# 12_LMS2_Power.net
KiCad netlist of a schematic drawn in Altium Designer
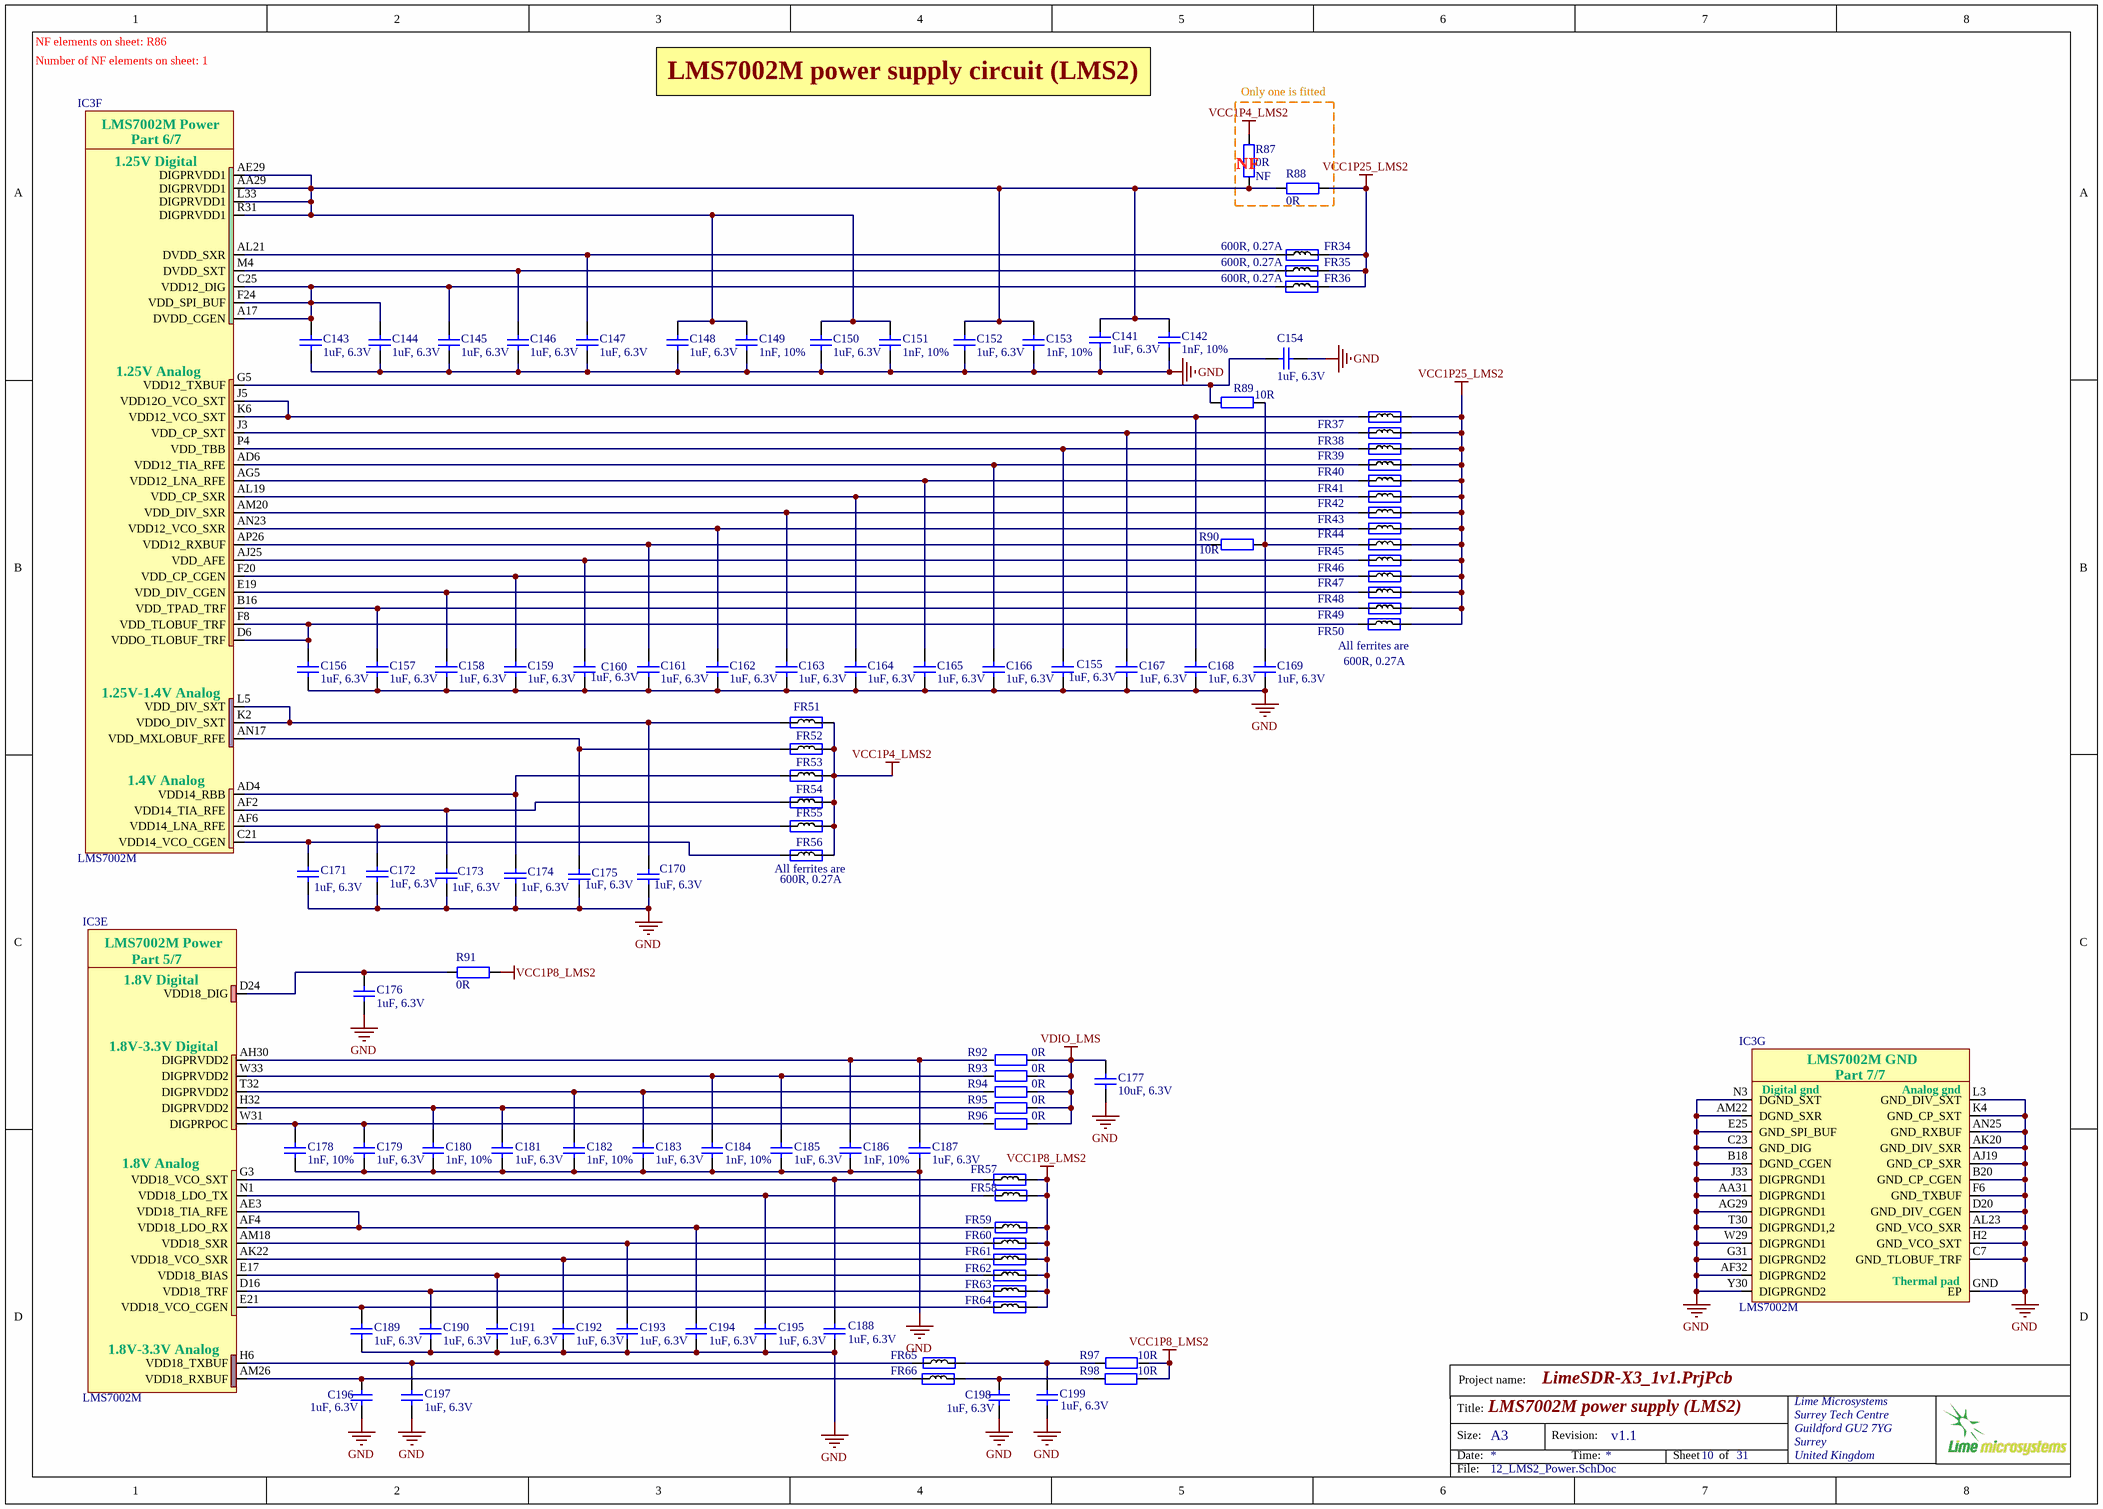
[diagram p0: 12_LMS2_Power.SchDoc]

(export (version "E")
  (design (tool "Eeschema 10.0.6"))
  (components
    (comp (ref "C141")
      (value "1uF, 6.3V")
      (footprint "CAP0201")
      (fields (field (name "TOLERANCE") "±20%") (field (name "MANUFACTURER") "TDK Corporation"))
      (libsource (lib "") (part "Cap_0402_1"))
    )
    (comp (ref "C142")
      (value "1nF, 10%")
      (footprint "CAP0201")
      (fields (field (name "TOLERANCE") "±10%") (field (name "MANUFACTURER") "TDK Corporation"))
      (libsource (lib "") (part "Cap_0402_1"))
    )
    (comp (ref "C143")
      (value "1uF, 6.3V")
      (footprint "CAP0201")
      (fields (field (name "TOLERANCE") "±20%") (field (name "MANUFACTURER") "TDK Corporation"))
      (libsource (lib "") (part "Cap_0402_2"))
    )
    (comp (ref "C144")
      (value "1uF, 6.3V")
      (footprint "CAP0201")
      (fields (field (name "TOLERANCE") "±20%") (field (name "MANUFACTURER") "TDK Corporation"))
      (libsource (lib "") (part "Cap_0402_2"))
    )
    (comp (ref "C145")
      (value "1uF, 6.3V")
      (footprint "CAP0201")
      (fields (field (name "TOLERANCE") "±20%") (field (name "MANUFACTURER") "TDK Corporation"))
      (libsource (lib "") (part "Cap_0402_2"))
    )
    (comp (ref "C146")
      (value "1uF, 6.3V")
      (footprint "CAP0201")
      (fields (field (name "TOLERANCE") "±20%") (field (name "MANUFACTURER") "TDK Corporation"))
      (libsource (lib "") (part "Cap_0402_1"))
    )
    (comp (ref "C147")
      (value "1uF, 6.3V")
      (footprint "CAP0201")
      (fields (field (name "TOLERANCE") "±20%") (field (name "MANUFACTURER") "TDK Corporation"))
      (libsource (lib "") (part "Cap_0402_2"))
    )
    (comp (ref "C148")
      (value "1uF, 6.3V")
      (footprint "CAP0201")
      (fields (field (name "TOLERANCE") "±20%") (field (name "MANUFACTURER") "TDK Corporation"))
      (libsource (lib "") (part "Cap_0402_1"))
    )
    (comp (ref "C149")
      (value "1nF, 10%")
      (footprint "CAP0201")
      (fields (field (name "TOLERANCE") "±10%") (field (name "MANUFACTURER") "TDK Corporation"))
      (libsource (lib "") (part "Cap_0402_1"))
    )
    (comp (ref "C150")
      (value "1uF, 6.3V")
      (footprint "CAP0201")
      (fields (field (name "TOLERANCE") "±20%") (field (name "MANUFACTURER") "TDK Corporation"))
      (libsource (lib "") (part "Cap_0402_1"))
    )
    (comp (ref "C151")
      (value "1nF, 10%")
      (footprint "CAP0201")
      (fields (field (name "TOLERANCE") "±10%") (field (name "MANUFACTURER") "TDK Corporation"))
      (libsource (lib "") (part "Cap_0402_1"))
    )
    (comp (ref "C152")
      (value "1uF, 6.3V")
      (footprint "CAP0201")
      (fields (field (name "TOLERANCE") "±20%") (field (name "MANUFACTURER") "TDK Corporation"))
      (libsource (lib "") (part "Cap_0402_1"))
    )
    (comp (ref "C153")
      (value "1nF, 10%")
      (footprint "CAP0201")
      (fields (field (name "TOLERANCE") "±10%") (field (name "MANUFACTURER") "TDK Corporation"))
      (libsource (lib "") (part "Cap_0402_1"))
    )
    (comp (ref "C154")
      (value "1uF, 6.3V")
      (footprint "CAP0201")
      (fields (field (name "TOLERANCE") "±20%") (field (name "MANUFACTURER") "TDK Corporation"))
      (libsource (lib "") (part "Cap_0402_4"))
    )
    (comp (ref "C155")
      (value "1uF, 6.3V")
      (footprint "CAP0201")
      (fields (field (name "TOLERANCE") "±20%") (field (name "MANUFACTURER") "TDK Corporation"))
      (libsource (lib "") (part "Cap_0402_2"))
    )
    (comp (ref "C156")
      (value "1uF, 6.3V")
      (footprint "CAP0201")
      (fields (field (name "TOLERANCE") "±20%") (field (name "MANUFACTURER") "TDK Corporation"))
      (libsource (lib "") (part "Cap_0402_2"))
    )
    (comp (ref "C157")
      (value "1uF, 6.3V")
      (footprint "CAP0201")
      (fields (field (name "TOLERANCE") "±20%") (field (name "MANUFACTURER") "TDK Corporation"))
      (libsource (lib "") (part "Cap_0402_2"))
    )
    (comp (ref "C158")
      (value "1uF, 6.3V")
      (footprint "CAP0201")
      (fields (field (name "TOLERANCE") "±20%") (field (name "MANUFACTURER") "TDK Corporation"))
      (libsource (lib "") (part "Cap_0402_2"))
    )
    (comp (ref "C159")
      (value "1uF, 6.3V")
      (footprint "CAP0201")
      (fields (field (name "TOLERANCE") "±20%") (field (name "MANUFACTURER") "TDK Corporation"))
      (libsource (lib "") (part "Cap_0402_1"))
    )
    (comp (ref "C160")
      (value "1uF, 6.3V")
      (footprint "CAP0201")
      (fields (field (name "TOLERANCE") "±20%") (field (name "MANUFACTURER") "TDK Corporation"))
      (libsource (lib "") (part "Cap_0402_2"))
    )
    (comp (ref "C161")
      (value "1uF, 6.3V")
      (footprint "CAP0201")
      (fields (field (name "TOLERANCE") "±20%") (field (name "MANUFACTURER") "TDK Corporation"))
      (libsource (lib "") (part "Cap_0402_2"))
    )
    (comp (ref "C162")
      (value "1uF, 6.3V")
      (footprint "CAP0201")
      (fields (field (name "TOLERANCE") "±20%") (field (name "MANUFACTURER") "TDK Corporation"))
      (libsource (lib "") (part "Cap_0402_2"))
    )
    (comp (ref "C163")
      (value "1uF, 6.3V")
      (footprint "CAP0201")
      (fields (field (name "TOLERANCE") "±20%") (field (name "MANUFACTURER") "TDK Corporation"))
      (libsource (lib "") (part "Cap_0402_2"))
    )
    (comp (ref "C164")
      (value "1uF, 6.3V")
      (footprint "CAP0201")
      (fields (field (name "TOLERANCE") "±20%") (field (name "MANUFACTURER") "TDK Corporation"))
      (libsource (lib "") (part "Cap_0402_2"))
    )
    (comp (ref "C165")
      (value "1uF, 6.3V")
      (footprint "CAP0201")
      (fields (field (name "TOLERANCE") "±20%") (field (name "MANUFACTURER") "TDK Corporation"))
      (libsource (lib "") (part "Cap_0402_2"))
    )
    (comp (ref "C166")
      (value "1uF, 6.3V")
      (footprint "CAP0201")
      (fields (field (name "TOLERANCE") "±20%") (field (name "MANUFACTURER") "TDK Corporation"))
      (libsource (lib "") (part "Cap_0402_1"))
    )
    (comp (ref "C167")
      (value "1uF, 6.3V")
      (footprint "CAP0201")
      (fields (field (name "TOLERANCE") "±20%") (field (name "MANUFACTURER") "TDK Corporation"))
      (libsource (lib "") (part "Cap_0402_2"))
    )
    (comp (ref "C168")
      (value "1uF, 6.3V")
      (footprint "CAP0201")
      (fields (field (name "TOLERANCE") "±20%") (field (name "MANUFACTURER") "TDK Corporation"))
      (libsource (lib "") (part "Cap_0402_1"))
    )
    (comp (ref "C169")
      (value "1uF, 6.3V")
      (footprint "CAP0201")
      (fields (field (name "TOLERANCE") "±20%") (field (name "MANUFACTURER") "TDK Corporation"))
      (libsource (lib "") (part "Cap_0402_1"))
    )
    (comp (ref "C170")
      (value "1uF, 6.3V")
      (footprint "CAP0201")
      (fields (field (name "TOLERANCE") "±20%") (field (name "MANUFACTURER") "TDK Corporation"))
      (libsource (lib "") (part "Cap_0402_2"))
    )
    (comp (ref "C171")
      (value "1uF, 6.3V")
      (footprint "CAP0201")
      (fields (field (name "TOLERANCE") "±20%") (field (name "MANUFACTURER") "TDK Corporation"))
      (libsource (lib "") (part "Cap_0402_2"))
    )
    (comp (ref "C172")
      (value "1uF, 6.3V")
      (footprint "CAP0201")
      (fields (field (name "TOLERANCE") "±20%") (field (name "MANUFACTURER") "TDK Corporation"))
      (libsource (lib "") (part "Cap_0402_2"))
    )
    (comp (ref "C173")
      (value "1uF, 6.3V")
      (footprint "CAP0201")
      (fields (field (name "TOLERANCE") "±20%") (field (name "MANUFACTURER") "TDK Corporation"))
      (libsource (lib "") (part "Cap_0402_3"))
    )
    (comp (ref "C174")
      (value "1uF, 6.3V")
      (footprint "CAP0201")
      (fields (field (name "TOLERANCE") "±20%") (field (name "MANUFACTURER") "TDK Corporation"))
      (libsource (lib "") (part "Cap_0402_3"))
    )
    (comp (ref "C175")
      (value "1uF, 6.3V")
      (footprint "CAP0201")
      (fields (field (name "TOLERANCE") "±20%") (field (name "MANUFACTURER") "TDK Corporation"))
      (libsource (lib "") (part "Cap_0402_2"))
    )
    (comp (ref "C176")
      (value "1uF, 6.3V")
      (footprint "CAP0201")
      (fields (field (name "TOLERANCE") "±20%") (field (name "MANUFACTURER") "TDK Corporation"))
      (libsource (lib "LimeMicroAltiumLib_schLib") (part "Cap_0402"))
    )
    (comp (ref "C177")
      (value "10uF, 6.3V")
      (footprint "CAP0603")
      (fields (field (name "TOLERANCE") "±20%") (field (name "MANUFACTURER") "Yageo"))
      (libsource (lib "LimeFPGAboard_schLib") (part "Cap_0603"))
    )
    (comp (ref "C178")
      (value "1nF, 10%")
      (footprint "CAP0201")
      (fields (field (name "TOLERANCE") "±10%") (field (name "MANUFACTURER") "TDK Corporation"))
      (libsource (lib "LimeMicroAltiumLib_schLib") (part "Cap_0402"))
    )
    (comp (ref "C179")
      (value "1uF, 6.3V")
      (footprint "CAP0201")
      (fields (field (name "TOLERANCE") "±20%") (field (name "MANUFACTURER") "TDK Corporation"))
      (libsource (lib "LimeMicroAltiumLib_schLib") (part "Cap_0402"))
    )
    (comp (ref "C180")
      (value "1nF, 10%")
      (footprint "CAP0201")
      (fields (field (name "TOLERANCE") "±10%") (field (name "MANUFACTURER") "TDK Corporation"))
      (libsource (lib "LimeMicroAltiumLib_schLib") (part "Cap_0402"))
    )
    (comp (ref "C181")
      (value "1uF, 6.3V")
      (footprint "CAP0201")
      (fields (field (name "TOLERANCE") "±20%") (field (name "MANUFACTURER") "TDK Corporation"))
      (libsource (lib "LimeMicroAltiumLib_schLib") (part "Cap_0402"))
    )
    (comp (ref "C182")
      (value "1nF, 10%")
      (footprint "CAP0201")
      (fields (field (name "TOLERANCE") "±10%") (field (name "MANUFACTURER") "TDK Corporation"))
      (libsource (lib "LimeMicroAltiumLib_schLib") (part "Cap_0402"))
    )
    (comp (ref "C183")
      (value "1uF, 6.3V")
      (footprint "CAP0201")
      (fields (field (name "TOLERANCE") "±20%") (field (name "MANUFACTURER") "TDK Corporation"))
      (libsource (lib "LimeMicroAltiumLib_schLib") (part "Cap_0402"))
    )
    (comp (ref "C184")
      (value "1nF, 10%")
      (footprint "CAP0201")
      (fields (field (name "TOLERANCE") "±10%") (field (name "MANUFACTURER") "TDK Corporation"))
      (libsource (lib "LimeMicroAltiumLib_schLib") (part "Cap_0402"))
    )
    (comp (ref "C185")
      (value "1uF, 6.3V")
      (footprint "CAP0201")
      (fields (field (name "TOLERANCE") "±20%") (field (name "MANUFACTURER") "TDK Corporation"))
      (libsource (lib "LimeMicroAltiumLib_schLib") (part "Cap_0402"))
    )
    (comp (ref "C186")
      (value "1nF, 10%")
      (footprint "CAP0201")
      (fields (field (name "TOLERANCE") "±10%") (field (name "MANUFACTURER") "TDK Corporation"))
      (libsource (lib "LimeMicroAltiumLib_schLib") (part "Cap_0402"))
    )
    (comp (ref "C187")
      (value "1uF, 6.3V")
      (footprint "CAP0201")
      (fields (field (name "TOLERANCE") "±20%") (field (name "MANUFACTURER") "TDK Corporation"))
      (libsource (lib "LimeMicroAltiumLib_schLib") (part "Cap_0402"))
    )
    (comp (ref "C188")
      (value "1uF, 6.3V")
      (footprint "CAP0201")
      (fields (field (name "TOLERANCE") "±20%") (field (name "MANUFACTURER") "TDK Corporation"))
      (libsource (lib "LimeMicroAltiumLib_schLib") (part "Cap_0402"))
    )
    (comp (ref "C189")
      (value "1uF, 6.3V")
      (footprint "CAP0201")
      (fields (field (name "TOLERANCE") "±20%") (field (name "MANUFACTURER") "TDK Corporation"))
      (libsource (lib "LimeMicroAltiumLib_schLib") (part "Cap_0402"))
    )
    (comp (ref "C190")
      (value "1uF, 6.3V")
      (footprint "CAP0201")
      (fields (field (name "TOLERANCE") "±20%") (field (name "MANUFACTURER") "TDK Corporation"))
      (libsource (lib "LimeMicroAltiumLib_schLib") (part "Cap_0402"))
    )
    (comp (ref "C191")
      (value "1uF, 6.3V")
      (footprint "CAP0201")
      (fields (field (name "TOLERANCE") "±20%") (field (name "MANUFACTURER") "TDK Corporation"))
      (libsource (lib "LimeMicroAltiumLib_schLib") (part "Cap_0402"))
    )
    (comp (ref "C192")
      (value "1uF, 6.3V")
      (footprint "CAP0201")
      (fields (field (name "TOLERANCE") "±20%") (field (name "MANUFACTURER") "TDK Corporation"))
      (libsource (lib "LimeMicroAltiumLib_schLib") (part "Cap_0402"))
    )
    (comp (ref "C193")
      (value "1uF, 6.3V")
      (footprint "CAP0201")
      (fields (field (name "TOLERANCE") "±20%") (field (name "MANUFACTURER") "TDK Corporation"))
      (libsource (lib "LimeMicroAltiumLib_schLib") (part "Cap_0402"))
    )
    (comp (ref "C194")
      (value "1uF, 6.3V")
      (footprint "CAP0201")
      (fields (field (name "TOLERANCE") "±20%") (field (name "MANUFACTURER") "TDK Corporation"))
      (libsource (lib "LimeMicroAltiumLib_schLib") (part "Cap_0402"))
    )
    (comp (ref "C195")
      (value "1uF, 6.3V")
      (footprint "CAP0201")
      (fields (field (name "TOLERANCE") "±20%") (field (name "MANUFACTURER") "TDK Corporation"))
      (libsource (lib "LimeMicroAltiumLib_schLib") (part "Cap_0402"))
    )
    (comp (ref "C196")
      (value "1uF, 6.3V")
      (footprint "CAP0201")
      (fields (field (name "TOLERANCE") "±20%") (field (name "MANUFACTURER") "TDK Corporation"))
      (libsource (lib "LimeMicroAltiumLib_schLib") (part "Cap_0402"))
    )
    (comp (ref "C197")
      (value "1uF, 6.3V")
      (footprint "CAP0201")
      (fields (field (name "TOLERANCE") "±20%") (field (name "MANUFACTURER") "TDK Corporation"))
      (libsource (lib "LimeMicroAltiumLib_schLib") (part "Cap_0402"))
    )
    (comp (ref "C198")
      (value "1uF, 6.3V")
      (footprint "CAP0201")
      (fields (field (name "TOLERANCE") "±20%") (field (name "MANUFACTURER") "TDK Corporation"))
      (libsource (lib "LimeMicroAltiumLib_schLib") (part "Cap_0402"))
    )
    (comp (ref "C199")
      (value "1uF, 6.3V")
      (footprint "CAP0201")
      (fields (field (name "TOLERANCE") "±20%") (field (name "MANUFACTURER") "TDK Corporation"))
      (libsource (lib "LimeMicroAltiumLib_schLib") (part "Cap_0402"))
    )
    (comp (ref "FR34")
      (value "600R, 0.27A")
      (footprint "RES0201")
      (fields (field (name "MANUFACTURER") "Taiyo Yuden"))
      (libsource (lib "") (part "Ferrite_1"))
    )
    (comp (ref "FR35")
      (value "600R, 0.27A")
      (footprint "RES0201")
      (fields (field (name "MANUFACTURER") "Taiyo Yuden"))
      (libsource (lib "LimeMicroAltiumLib_schLib") (part "Ferrite"))
    )
    (comp (ref "FR36")
      (value "600R, 0.27A")
      (footprint "RES0201")
      (fields (field (name "MANUFACTURER") "Taiyo Yuden"))
      (libsource (lib "LimeMicroAltiumLib_schLib") (part "Ferrite"))
    )
    (comp (ref "FR37")
      (value "600R, 0.27A")
      (footprint "RES0201")
      (fields (field (name "MANUFACTURER") "Taiyo Yuden"))
      (libsource (lib "") (part "Ferrite_1"))
    )
    (comp (ref "FR38")
      (value "600R, 0.27A")
      (footprint "RES0201")
      (fields (field (name "MANUFACTURER") "Taiyo Yuden"))
      (libsource (lib "") (part "Ferrite_1"))
    )
    (comp (ref "FR39")
      (value "600R, 0.27A")
      (footprint "RES0201")
      (fields (field (name "MANUFACTURER") "Taiyo Yuden"))
      (libsource (lib "") (part "Ferrite_1"))
    )
    (comp (ref "FR40")
      (value "600R, 0.27A")
      (footprint "RES0201")
      (fields (field (name "MANUFACTURER") "Taiyo Yuden"))
      (libsource (lib "") (part "Ferrite_1"))
    )
    (comp (ref "FR41")
      (value "600R, 0.27A")
      (footprint "RES0201")
      (fields (field (name "MANUFACTURER") "Taiyo Yuden"))
      (libsource (lib "") (part "Ferrite_1"))
    )
    (comp (ref "FR42")
      (value "600R, 0.27A")
      (footprint "RES0201")
      (fields (field (name "MANUFACTURER") "Taiyo Yuden"))
      (libsource (lib "") (part "Ferrite_1"))
    )
    (comp (ref "FR43")
      (value "600R, 0.27A")
      (footprint "RES0201")
      (fields (field (name "MANUFACTURER") "Taiyo Yuden"))
      (libsource (lib "") (part "Ferrite_1"))
    )
    (comp (ref "FR44")
      (value "600R, 0.27A")
      (footprint "RES0201")
      (fields (field (name "MANUFACTURER") "Taiyo Yuden"))
      (libsource (lib "") (part "Ferrite_1"))
    )
    (comp (ref "FR45")
      (value "600R, 0.27A")
      (footprint "RES0201")
      (fields (field (name "MANUFACTURER") "Taiyo Yuden"))
      (libsource (lib "") (part "Ferrite_1"))
    )
    (comp (ref "FR46")
      (value "600R, 0.27A")
      (footprint "RES0201")
      (fields (field (name "MANUFACTURER") "Taiyo Yuden"))
      (libsource (lib "") (part "Ferrite_1"))
    )
    (comp (ref "FR47")
      (value "600R, 0.27A")
      (footprint "RES0201")
      (fields (field (name "MANUFACTURER") "Taiyo Yuden"))
      (libsource (lib "") (part "Ferrite_1"))
    )
    (comp (ref "FR48")
      (value "600R, 0.27A")
      (footprint "RES0201")
      (fields (field (name "MANUFACTURER") "Taiyo Yuden"))
      (libsource (lib "") (part "Ferrite_1"))
    )
    (comp (ref "FR49")
      (value "600R, 0.27A")
      (footprint "RES0201")
      (fields (field (name "MANUFACTURER") "Taiyo Yuden"))
      (libsource (lib "") (part "Ferrite_1"))
    )
    (comp (ref "FR50")
      (value "600R, 0.27A")
      (footprint "RES0201")
      (fields (field (name "MANUFACTURER") "Taiyo Yuden"))
      (libsource (lib "LimeMicroAltiumLib_schLib") (part "Ferrite"))
    )
    (comp (ref "FR51")
      (value "600R, 0.27A")
      (footprint "RES0201")
      (fields (field (name "MANUFACTURER") "Taiyo Yuden"))
      (libsource (lib "LimeMicroAltiumLib_schLib") (part "Ferrite"))
    )
    (comp (ref "FR52")
      (value "600R, 0.27A")
      (footprint "RES0201")
      (fields (field (name "MANUFACTURER") "Taiyo Yuden"))
      (libsource (lib "LimeMicroAltiumLib_schLib") (part "Ferrite"))
    )
    (comp (ref "FR53")
      (value "600R, 0.27A")
      (footprint "RES0201")
      (fields (field (name "MANUFACTURER") "Taiyo Yuden"))
      (libsource (lib "LimeMicroAltiumLib_schLib") (part "Ferrite"))
    )
    (comp (ref "FR54")
      (value "600R, 0.27A")
      (footprint "RES0201")
      (fields (field (name "MANUFACTURER") "Taiyo Yuden"))
      (libsource (lib "LimeMicroAltiumLib_schLib") (part "Ferrite"))
    )
    (comp (ref "FR55")
      (value "600R, 0.27A")
      (footprint "RES0201")
      (fields (field (name "MANUFACTURER") "Taiyo Yuden"))
      (libsource (lib "LimeMicroAltiumLib_schLib") (part "Ferrite"))
    )
    (comp (ref "FR56")
      (value "600R, 0.27A")
      (footprint "RES0201")
      (fields (field (name "MANUFACTURER") "Taiyo Yuden"))
      (libsource (lib "LimeMicroAltiumLib_schLib") (part "Ferrite"))
    )
    (comp (ref "FR57")
      (value "600R, 0.27A")
      (footprint "RES0201")
      (fields (field (name "MANUFACTURER") "Taiyo Yuden"))
      (libsource (lib "LimeMicroAltiumLib_schLib") (part "Ferrite"))
    )
    (comp (ref "FR58")
      (value "600R, 0.27A")
      (footprint "RES0201")
      (fields (field (name "MANUFACTURER") "Taiyo Yuden"))
      (libsource (lib "") (part "Ferrite_2"))
    )
    (comp (ref "FR59")
      (value "600R, 0.27A")
      (footprint "RES0201")
      (fields (field (name "MANUFACTURER") "Taiyo Yuden"))
      (libsource (lib "") (part "Ferrite_2"))
    )
    (comp (ref "FR60")
      (value "600R, 0.27A")
      (footprint "RES0201")
      (fields (field (name "MANUFACTURER") "Taiyo Yuden"))
      (libsource (lib "LimeMicroAltiumLib_schLib") (part "Ferrite"))
    )
    (comp (ref "FR61")
      (value "600R, 0.27A")
      (footprint "RES0201")
      (fields (field (name "MANUFACTURER") "Taiyo Yuden"))
      (libsource (lib "LimeMicroAltiumLib_schLib") (part "Ferrite"))
    )
    (comp (ref "FR62")
      (value "600R, 0.27A")
      (footprint "RES0201")
      (fields (field (name "MANUFACTURER") "Taiyo Yuden"))
      (libsource (lib "LimeMicroAltiumLib_schLib") (part "Ferrite"))
    )
    (comp (ref "FR63")
      (value "600R, 0.27A")
      (footprint "RES0201")
      (fields (field (name "MANUFACTURER") "Taiyo Yuden"))
      (libsource (lib "LimeMicroAltiumLib_schLib") (part "Ferrite"))
    )
    (comp (ref "FR64")
      (value "600R, 0.27A")
      (footprint "RES0201")
      (fields (field (name "MANUFACTURER") "Taiyo Yuden"))
      (libsource (lib "LimeMicroAltiumLib_schLib") (part "Ferrite"))
    )
    (comp (ref "FR65")
      (value "600R, 0.27A")
      (footprint "RES0201")
      (fields (field (name "MANUFACTURER") "Taiyo Yuden"))
      (libsource (lib "") (part "Ferrite_2"))
    )
    (comp (ref "FR66")
      (value "600R, 0.27A")
      (footprint "RES0201")
      (fields (field (name "MANUFACTURER") "Taiyo Yuden"))
      (libsource (lib "LimeMicroAltiumLib_schLib") (part "Ferrite"))
    )
    (comp (ref "IC3")
      (value "LMS7002M")
      (footprint "LMS7002M_v5")
      (description "Schematic symbol revision 4. Default footprint - 0.31mm pad")
      (fields (field (name "MANUFACTURER") "Lime Microsystems"))
      (libsource (lib "LimeMicroAltiumLib_schLib_r04") (part "LMS7002Mr4"))
    )
    (comp (ref "R87")
      (value "0R")
      (footprint "RES0402")
      (fields
        (field (name "ASSEMBLY INFO") "NF")
        (field (name "MANUFACTURER") "Yageo")
        (field (name "TOLERANCE") "Jumper")
      )
      (libsource (lib "LimeMicroAltiumLib_schLib") (part "Res_0402"))
    )
    (comp (ref "R88")
      (value "0R")
      (footprint "RES0402")
      (fields (field (name "MANUFACTURER") "Yageo") (field (name "TOLERANCE") "Jumper"))
      (libsource (lib "") (part "Res_0402_1"))
    )
    (comp (ref "R89")
      (value "10R")
      (footprint "RES0201")
      (fields
        (field (name "MANUFACTURER") "Panasonic Electronic Components")
        (field (name "TOLERANCE") "±1%")
      )
      (libsource (lib "LimeMicroAltiumLib_schLib") (part "Res_0402"))
    )
    (comp (ref "R90")
      (value "10R")
      (footprint "RES0201")
      (fields
        (field (name "MANUFACTURER") "Panasonic Electronic Components")
        (field (name "TOLERANCE") "±1%")
      )
      (libsource (lib "LimeMicroAltiumLib_schLib") (part "Res_0402"))
    )
    (comp (ref "R91")
      (value "0R")
      (footprint "RES0201")
      (fields (field (name "MANUFACTURER") "Rohm Semiconductor") (field (name "TOLERANCE") "Jumper"))
      (libsource (lib "LimeMicroAltiumLib_schLib") (part "Res_0402"))
    )
    (comp (ref "R92")
      (value "0R")
      (footprint "RES0402")
      (fields (field (name "MANUFACTURER") "Yageo") (field (name "TOLERANCE") "Jumper"))
      (libsource (lib "LimeMicroAltiumLib_schLib") (part "Res_0402"))
    )
    (comp (ref "R93")
      (value "0R")
      (footprint "RES0402")
      (fields (field (name "MANUFACTURER") "Yageo") (field (name "TOLERANCE") "Jumper"))
      (libsource (lib "LimeMicroAltiumLib_schLib") (part "Res_0402"))
    )
    (comp (ref "R94")
      (value "0R")
      (footprint "RES0402")
      (fields (field (name "MANUFACTURER") "Yageo") (field (name "TOLERANCE") "Jumper"))
      (libsource (lib "LimeMicroAltiumLib_schLib") (part "Res_0402"))
    )
    (comp (ref "R95")
      (value "0R")
      (footprint "RES0402")
      (fields (field (name "MANUFACTURER") "Yageo") (field (name "TOLERANCE") "Jumper"))
      (libsource (lib "LimeMicroAltiumLib_schLib") (part "Res_0402"))
    )
    (comp (ref "R96")
      (value "0R")
      (footprint "RES0402")
      (fields (field (name "MANUFACTURER") "Yageo") (field (name "TOLERANCE") "Jumper"))
      (libsource (lib "LimeMicroAltiumLib_schLib") (part "Res_0402"))
    )
    (comp (ref "R97")
      (value "10R")
      (footprint "RES0201")
      (fields
        (field (name "MANUFACTURER") "Panasonic Electronic Components")
        (field (name "TOLERANCE") "±1%")
      )
      (libsource (lib "LimeMicroAltiumLib_schLib") (part "Res_0402"))
    )
    (comp (ref "R98")
      (value "10R")
      (footprint "RES0201")
      (fields
        (field (name "MANUFACTURER") "Panasonic Electronic Components")
        (field (name "TOLERANCE") "±1%")
      )
      (libsource (lib "LimeMicroAltiumLib_schLib") (part "Res_0402"))
    )
  )
  (nets
    (net (code "1") (name "GND") (class "Default")
      (node (ref "C141") (pin "2") (pinfunction "2_2") (pintype "passive"))
      (node (ref "C142") (pin "2") (pinfunction "2_2") (pintype "passive"))
      (node (ref "C143") (pin "2") (pinfunction "2_2") (pintype "passive"))
      (node (ref "C144") (pin "2") (pinfunction "2_2") (pintype "passive"))
      (node (ref "C145") (pin "2") (pinfunction "2_2") (pintype "passive"))
      (node (ref "C146") (pin "1") (pinfunction "1_1") (pintype "passive"))
      (node (ref "C147") (pin "2") (pinfunction "2_2") (pintype "passive"))
      (node (ref "C148") (pin "2") (pinfunction "2_2") (pintype "passive"))
      (node (ref "C149") (pin "2") (pinfunction "2_2") (pintype "passive"))
      (node (ref "C150") (pin "2") (pinfunction "2_2") (pintype "passive"))
      (node (ref "C151") (pin "2") (pinfunction "2_2") (pintype "passive"))
      (node (ref "C152") (pin "2") (pinfunction "2_2") (pintype "passive"))
      (node (ref "C153") (pin "2") (pinfunction "2_2") (pintype "passive"))
      (node (ref "C154") (pin "2") (pinfunction "2_2") (pintype "passive"))
      (node (ref "C155") (pin "2") (pinfunction "2_2") (pintype "passive"))
      (node (ref "C156") (pin "2") (pinfunction "2_2") (pintype "passive"))
      (node (ref "C157") (pin "2") (pinfunction "2_2") (pintype "passive"))
      (node (ref "C158") (pin "2") (pinfunction "2_2") (pintype "passive"))
      (node (ref "C159") (pin "1") (pinfunction "1_1") (pintype "passive"))
      (node (ref "C160") (pin "2") (pinfunction "2_2") (pintype "passive"))
      (node (ref "C161") (pin "2") (pinfunction "2_2") (pintype "passive"))
      (node (ref "C162") (pin "2") (pinfunction "2_2") (pintype "passive"))
      (node (ref "C163") (pin "2") (pinfunction "2_2") (pintype "passive"))
      (node (ref "C164") (pin "2") (pinfunction "2_2") (pintype "passive"))
      (node (ref "C165") (pin "2") (pinfunction "2_2") (pintype "passive"))
      (node (ref "C166") (pin "1") (pinfunction "1_1") (pintype "passive"))
      (node (ref "C167") (pin "2") (pinfunction "2_2") (pintype "passive"))
      (node (ref "C168") (pin "1") (pinfunction "1_1") (pintype "passive"))
      (node (ref "C169") (pin "1") (pinfunction "1_1") (pintype "passive"))
      (node (ref "C170") (pin "2") (pinfunction "2_2") (pintype "passive"))
      (node (ref "C171") (pin "2") (pinfunction "2_2") (pintype "passive"))
      (node (ref "C172") (pin "2") (pinfunction "2_2") (pintype "passive"))
      (node (ref "C173") (pin "2") (pinfunction "2_2") (pintype "passive"))
      (node (ref "C174") (pin "2") (pinfunction "2_2") (pintype "passive"))
      (node (ref "C175") (pin "2") (pinfunction "2_2") (pintype "passive"))
      (node (ref "C176") (pin "2") (pinfunction "2_2") (pintype "passive"))
      (node (ref "C177") (pin "1") (pinfunction "1_1") (pintype "passive"))
      (node (ref "C178") (pin "2") (pinfunction "2_2") (pintype "passive"))
      (node (ref "C179") (pin "2") (pinfunction "2_2") (pintype "passive"))
      (node (ref "C180") (pin "2") (pinfunction "2_2") (pintype "passive"))
      (node (ref "C181") (pin "2") (pinfunction "2_2") (pintype "passive"))
      (node (ref "C182") (pin "2") (pinfunction "2_2") (pintype "passive"))
      (node (ref "C183") (pin "2") (pinfunction "2_2") (pintype "passive"))
      (node (ref "C184") (pin "2") (pinfunction "2_2") (pintype "passive"))
      (node (ref "C185") (pin "2") (pinfunction "2_2") (pintype "passive"))
      (node (ref "C186") (pin "2") (pinfunction "2_2") (pintype "passive"))
      (node (ref "C187") (pin "2") (pinfunction "2_2") (pintype "passive"))
      (node (ref "C188") (pin "2") (pinfunction "2_2") (pintype "passive"))
      (node (ref "C189") (pin "2") (pinfunction "2_2") (pintype "passive"))
      (node (ref "C190") (pin "2") (pinfunction "2_2") (pintype "passive"))
      (node (ref "C191") (pin "2") (pinfunction "2_2") (pintype "passive"))
      (node (ref "C192") (pin "2") (pinfunction "2_2") (pintype "passive"))
      (node (ref "C193") (pin "2") (pinfunction "2_2") (pintype "passive"))
      (node (ref "C194") (pin "2") (pinfunction "2_2") (pintype "passive"))
      (node (ref "C195") (pin "2") (pinfunction "2_2") (pintype "passive"))
      (node (ref "C196") (pin "2") (pinfunction "2_2") (pintype "passive"))
      (node (ref "C197") (pin "2") (pinfunction "2_2") (pintype "passive"))
      (node (ref "C198") (pin "2") (pinfunction "2_2") (pintype "passive"))
      (node (ref "C199") (pin "2") (pinfunction "2_2") (pintype "passive"))
      (node (ref "IC3") (pin "AA31") (pinfunction "DIGPRGND1_AA31") (pintype "passive"))
      (node (ref "IC3") (pin "AF32") (pinfunction "DIGPRGND2_AF32") (pintype "passive"))
      (node (ref "IC3") (pin "AG29") (pinfunction "DIGPRGND1_AG29") (pintype "passive"))
      (node (ref "IC3") (pin "AJ19") (pinfunction "GND_CP_SXR_AJ19") (pintype "passive"))
      (node (ref "IC3") (pin "AK20") (pinfunction "GND_DIV_SXR_AK20") (pintype "passive"))
      (node (ref "IC3") (pin "AL23") (pinfunction "GND_VCO_SXR_AL23") (pintype "passive"))
      (node (ref "IC3") (pin "AM22") (pinfunction "DGND_SXR_AM22") (pintype "passive"))
      (node (ref "IC3") (pin "AN25") (pinfunction "GND_RXBUF_AN25") (pintype "passive"))
      (node (ref "IC3") (pin "B18") (pinfunction "DGND_CGEN_B18") (pintype "passive"))
      (node (ref "IC3") (pin "B20") (pinfunction "GND_CP_CGEN_B20") (pintype "passive"))
      (node (ref "IC3") (pin "C23") (pinfunction "GND_DIG_C23") (pintype "passive"))
      (node (ref "IC3") (pin "C7") (pinfunction "GND_TLOBUF_TRF_C7") (pintype "passive"))
      (node (ref "IC3") (pin "D20") (pinfunction "GND_DIV_CGEN_D20") (pintype "passive"))
      (node (ref "IC3") (pin "E25") (pinfunction "GND_SPI_BUF_E25") (pintype "passive"))
      (node (ref "IC3") (pin "F6") (pinfunction "GND_TXBUF_F6") (pintype "passive"))
      (node (ref "IC3") (pin "G31") (pinfunction "DIGPRGND2_G31") (pintype "passive"))
      (node (ref "IC3") (pin "GND") (pinfunction "EP_GND") (pintype "passive"))
      (node (ref "IC3") (pin "H2") (pinfunction "GND_VCO_SXT_H2") (pintype "passive"))
      (node (ref "IC3") (pin "J33") (pinfunction "DIGPRGND1_J33") (pintype "passive"))
      (node (ref "IC3") (pin "K4") (pinfunction "GND_CP_SXT_K4") (pintype "passive"))
      (node (ref "IC3") (pin "L3") (pinfunction "GND_DIV_SXT_L3") (pintype "passive"))
      (node (ref "IC3") (pin "N3") (pinfunction "DGND_SXT_N3") (pintype "passive"))
      (node (ref "IC3") (pin "T30") (pinfunction "DIGPRGND1,2_T30") (pintype "passive"))
      (node (ref "IC3") (pin "W29") (pinfunction "DIGPRGND1_W29") (pintype "passive"))
      (node (ref "IC3") (pin "Y30") (pinfunction "DIGPRGND2_Y30") (pintype "passive"))
    )
    (net (code "2") (name "Net-(C141-Pad1)") (class "Default")
      (node (ref "C141") (pin "1") (pinfunction "1_1") (pintype "passive"))
      (node (ref "C142") (pin "1") (pinfunction "1_1") (pintype "passive"))
      (node (ref "C148") (pin "1") (pinfunction "1_1") (pintype "passive"))
      (node (ref "C149") (pin "1") (pinfunction "1_1") (pintype "passive"))
      (node (ref "C150") (pin "1") (pinfunction "1_1") (pintype "passive"))
      (node (ref "C151") (pin "1") (pinfunction "1_1") (pintype "passive"))
      (node (ref "C152") (pin "1") (pinfunction "1_1") (pintype "passive"))
      (node (ref "C153") (pin "1") (pinfunction "1_1") (pintype "passive"))
      (node (ref "IC3") (pin "AA29") (pinfunction "DIGPRVDD1_AA29") (pintype "power_in"))
      (node (ref "IC3") (pin "AE29") (pinfunction "DIGPRVDD1_AE29") (pintype "power_in"))
      (node (ref "IC3") (pin "L33") (pinfunction "DIGPRVDD1_L33") (pintype "power_in"))
      (node (ref "IC3") (pin "R31") (pinfunction "DIGPRVDD1_R31") (pintype "power_in"))
      (node (ref "R87") (pin "2") (pinfunction "2_2") (pintype "passive"))
      (node (ref "R88") (pin "2") (pinfunction "2_2") (pintype "passive"))
    )
    (net (code "3") (name "Net-(C169-Pad2)") (class "Default")
      (node (ref "C169") (pin "2") (pinfunction "2_2") (pintype "passive"))
      (node (ref "FR45") (pin "1") (pinfunction "1_1") (pintype "passive"))
      (node (ref "R89") (pin "2") (pinfunction "2_2") (pintype "passive"))
      (node (ref "R90") (pin "2") (pinfunction "2_2") (pintype "passive"))
    )
    (net (code "4") (name "Net-(C180-Pad1)") (class "Default")
      (node (ref "C180") (pin "1") (pinfunction "1_1") (pintype "passive"))
      (node (ref "C181") (pin "1") (pinfunction "1_1") (pintype "passive"))
      (node (ref "IC3") (pin "H32") (pinfunction "DIGPRVDD2_H32") (pintype "power_in"))
      (node (ref "R95") (pin "2") (pinfunction "2_2") (pintype "passive"))
    )
    (net (code "5") (name "Net-(C182-Pad1)") (class "Default")
      (node (ref "C182") (pin "1") (pinfunction "1_1") (pintype "passive"))
      (node (ref "C183") (pin "1") (pinfunction "1_1") (pintype "passive"))
      (node (ref "IC3") (pin "T32") (pinfunction "DIGPRVDD2_T32") (pintype "power_in"))
      (node (ref "R94") (pin "2") (pinfunction "2_2") (pintype "passive"))
    )
    (net (code "6") (name "Net-(C184-Pad1)") (class "Default")
      (node (ref "C184") (pin "1") (pinfunction "1_1") (pintype "passive"))
      (node (ref "C185") (pin "1") (pinfunction "1_1") (pintype "passive"))
      (node (ref "IC3") (pin "W33") (pinfunction "DIGPRVDD2_W33") (pintype "power_in"))
      (node (ref "R93") (pin "2") (pinfunction "2_2") (pintype "passive"))
    )
    (net (code "7") (name "Net-(C186-Pad1)") (class "Default")
      (node (ref "C186") (pin "1") (pinfunction "1_1") (pintype "passive"))
      (node (ref "C187") (pin "1") (pinfunction "1_1") (pintype "passive"))
      (node (ref "IC3") (pin "AH30") (pinfunction "DIGPRVDD2_AH30") (pintype "power_in"))
      (node (ref "R92") (pin "2") (pinfunction "2_2") (pintype "passive"))
    )
    (net (code "8") (name "Net-(C198-Pad1)") (class "Default")
      (node (ref "C198") (pin "1") (pinfunction "1_1") (pintype "passive"))
      (node (ref "FR66") (pin "2") (pinfunction "2_2") (pintype "passive"))
      (node (ref "R98") (pin "2") (pinfunction "2_2") (pintype "passive"))
    )
    (net (code "9") (name "Net-(C199-Pad1)") (class "Default")
      (node (ref "C199") (pin "1") (pinfunction "1_1") (pintype "passive"))
      (node (ref "FR65") (pin "1") (pinfunction "1_1") (pintype "passive"))
      (node (ref "R97") (pin "1") (pinfunction "1_1") (pintype "passive"))
    )
    (net (code "10") (name "Net-(IC3E-DIGPRPOC)") (class "Default")
      (node (ref "C178") (pin "1") (pinfunction "1_1") (pintype "passive"))
      (node (ref "C179") (pin "1") (pinfunction "1_1") (pintype "passive"))
      (node (ref "IC3") (pin "W31") (pinfunction "DIGPRPOC_W31") (pintype "power_in"))
      (node (ref "R96") (pin "2") (pinfunction "2_2") (pintype "passive"))
    )
    (net (code "11") (name "Net-(IC3E-VDD18_BIAS)") (class "Default")
      (node (ref "C191") (pin "1") (pinfunction "1_1") (pintype "passive"))
      (node (ref "FR62") (pin "1") (pinfunction "1_1") (pintype "passive"))
      (node (ref "IC3") (pin "E17") (pinfunction "VDD18_BIAS_E17") (pintype "power_in"))
    )
    (net (code "12") (name "Net-(IC3E-VDD18_DIG)") (class "Default")
      (node (ref "C176") (pin "1") (pinfunction "1_1") (pintype "passive"))
      (node (ref "IC3") (pin "D24") (pinfunction "VDD18_DIG_D24") (pintype "power_in"))
      (node (ref "R91") (pin "1") (pinfunction "1_1") (pintype "passive"))
    )
    (net (code "13") (name "Net-(IC3E-VDD18_LDO_RX)") (class "Default")
      (node (ref "C194") (pin "1") (pinfunction "1_1") (pintype "passive"))
      (node (ref "FR59") (pin "2") (pinfunction "2_2") (pintype "passive"))
      (node (ref "IC3") (pin "AE3") (pinfunction "VDD18_TIA_RFE_AE3") (pintype "power_in"))
      (node (ref "IC3") (pin "AF4") (pinfunction "VDD18_LDO_RX_AF4") (pintype "power_in"))
    )
    (net (code "14") (name "Net-(IC3E-VDD18_LDO_TX)") (class "Default")
      (node (ref "C195") (pin "1") (pinfunction "1_1") (pintype "passive"))
      (node (ref "FR58") (pin "2") (pinfunction "2_2") (pintype "passive"))
      (node (ref "IC3") (pin "N1") (pinfunction "VDD18_LDO_TX_N1") (pintype "power_in"))
    )
    (net (code "15") (name "Net-(IC3E-VDD18_RXBUF)") (class "Default")
      (node (ref "C196") (pin "1") (pinfunction "1_1") (pintype "passive"))
      (node (ref "FR66") (pin "1") (pinfunction "1_1") (pintype "passive"))
      (node (ref "IC3") (pin "AM26") (pinfunction "VDD18_RXBUF_AM26") (pintype "power_in"))
    )
    (net (code "16") (name "Net-(IC3E-VDD18_SXR)") (class "Default")
      (node (ref "C193") (pin "1") (pinfunction "1_1") (pintype "passive"))
      (node (ref "FR60") (pin "1") (pinfunction "1_1") (pintype "passive"))
      (node (ref "IC3") (pin "AM18") (pinfunction "VDD18_SXR_AM18") (pintype "power_in"))
    )
    (net (code "17") (name "Net-(IC3E-VDD18_TRF)") (class "Default")
      (node (ref "C190") (pin "1") (pinfunction "1_1") (pintype "passive"))
      (node (ref "FR63") (pin "1") (pinfunction "1_1") (pintype "passive"))
      (node (ref "IC3") (pin "D16") (pinfunction "VDD18_TRF_D16") (pintype "power_in"))
    )
    (net (code "18") (name "Net-(IC3E-VDD18_TXBUF)") (class "Default")
      (node (ref "C197") (pin "1") (pinfunction "1_1") (pintype "passive"))
      (node (ref "FR65") (pin "2") (pinfunction "2_2") (pintype "passive"))
      (node (ref "IC3") (pin "H6") (pinfunction "VDD18_TXBUF_H6") (pintype "power_in"))
    )
    (net (code "19") (name "Net-(IC3E-VDD18_VCO_CGEN)") (class "Default")
      (node (ref "C189") (pin "1") (pinfunction "1_1") (pintype "passive"))
      (node (ref "FR64") (pin "1") (pinfunction "1_1") (pintype "passive"))
      (node (ref "IC3") (pin "E21") (pinfunction "VDD18_VCO_CGEN_E21") (pintype "power_in"))
    )
    (net (code "20") (name "Net-(IC3E-VDD18_VCO_SXR)") (class "Default")
      (node (ref "C192") (pin "1") (pinfunction "1_1") (pintype "passive"))
      (node (ref "FR61") (pin "1") (pinfunction "1_1") (pintype "passive"))
      (node (ref "IC3") (pin "AK22") (pinfunction "VDD18_VCO_SXR_AK22") (pintype "power_in"))
    )
    (net (code "21") (name "Net-(IC3E-VDD18_VCO_SXT)") (class "Default")
      (node (ref "C188") (pin "1") (pinfunction "1_1") (pintype "passive"))
      (node (ref "FR57") (pin "1") (pinfunction "1_1") (pintype "passive"))
      (node (ref "IC3") (pin "G3") (pinfunction "VDD18_VCO_SXT_G3") (pintype "power_in"))
    )
    (net (code "22") (name "Net-(IC3F-DVDD_CGEN)") (class "Default")
      (node (ref "C143") (pin "1") (pinfunction "1_1") (pintype "passive"))
      (node (ref "C144") (pin "1") (pinfunction "1_1") (pintype "passive"))
      (node (ref "C145") (pin "1") (pinfunction "1_1") (pintype "passive"))
      (node (ref "FR36") (pin "1") (pinfunction "1_1") (pintype "passive"))
      (node (ref "IC3") (pin "A17") (pinfunction "DVDD_CGEN_A17") (pintype "power_in"))
      (node (ref "IC3") (pin "C25") (pinfunction "VDD12_DIG_C25") (pintype "power_in"))
      (node (ref "IC3") (pin "F24") (pinfunction "VDD_SPI_BUF_F24") (pintype "power_in"))
    )
    (net (code "23") (name "Net-(IC3F-DVDD_SXR)") (class "Default")
      (node (ref "C147") (pin "1") (pinfunction "1_1") (pintype "passive"))
      (node (ref "FR34") (pin "1") (pinfunction "1_1") (pintype "passive"))
      (node (ref "IC3") (pin "AL21") (pinfunction "DVDD_SXR_AL21") (pintype "power_in"))
    )
    (net (code "24") (name "Net-(IC3F-DVDD_SXT)") (class "Default")
      (node (ref "C146") (pin "2") (pinfunction "2_2") (pintype "passive"))
      (node (ref "FR35") (pin "1") (pinfunction "1_1") (pintype "passive"))
      (node (ref "IC3") (pin "M4") (pinfunction "DVDD_SXT_M4") (pintype "power_in"))
    )
    (net (code "25") (name "Net-(IC3F-VDD12O_VCO_SXT)") (class "Default")
      (node (ref "C168") (pin "2") (pinfunction "2_2") (pintype "passive"))
      (node (ref "FR37") (pin "1") (pinfunction "1_1") (pintype "passive"))
      (node (ref "IC3") (pin "J5") (pinfunction "VDD12O_VCO_SXT_J5") (pintype "power_in"))
      (node (ref "IC3") (pin "K6") (pinfunction "VDD12_VCO_SXT_K6") (pintype "power_in"))
    )
    (net (code "26") (name "Net-(IC3F-VDD12_LNA_RFE)") (class "Default")
      (node (ref "C165") (pin "1") (pinfunction "1_1") (pintype "passive"))
      (node (ref "FR41") (pin "1") (pinfunction "1_1") (pintype "passive"))
      (node (ref "IC3") (pin "AG5") (pinfunction "VDD12_LNA_RFE_AG5") (pintype "power_in"))
    )
    (net (code "27") (name "Net-(IC3F-VDD12_RXBUF)") (class "Default")
      (node (ref "C161") (pin "1") (pinfunction "1_1") (pintype "passive"))
      (node (ref "IC3") (pin "AP26") (pinfunction "VDD12_RXBUF_AP26") (pintype "power_in"))
      (node (ref "R90") (pin "1") (pinfunction "1_1") (pintype "passive"))
    )
    (net (code "28") (name "Net-(IC3F-VDD12_TIA_RFE)") (class "Default")
      (node (ref "C166") (pin "2") (pinfunction "2_2") (pintype "passive"))
      (node (ref "FR40") (pin "1") (pinfunction "1_1") (pintype "passive"))
      (node (ref "IC3") (pin "AD6") (pinfunction "VDD12_TIA_RFE_AD6") (pintype "power_in"))
    )
    (net (code "29") (name "Net-(IC3F-VDD12_TXBUF)") (class "Default")
      (node (ref "C154") (pin "1") (pinfunction "1_1") (pintype "passive"))
      (node (ref "IC3") (pin "G5") (pinfunction "VDD12_TXBUF_G5") (pintype "power_in"))
      (node (ref "R89") (pin "1") (pinfunction "1_1") (pintype "passive"))
    )
    (net (code "30") (name "Net-(IC3F-VDD12_VCO_SXR)") (class "Default")
      (node (ref "C162") (pin "1") (pinfunction "1_1") (pintype "passive"))
      (node (ref "FR44") (pin "1") (pinfunction "1_1") (pintype "passive"))
      (node (ref "IC3") (pin "AN23") (pinfunction "VDD12_VCO_SXR_AN23") (pintype "power_in"))
    )
    (net (code "31") (name "Net-(IC3F-VDD14_LNA_RFE)") (class "Default")
      (node (ref "C172") (pin "1") (pinfunction "1_1") (pintype "passive"))
      (node (ref "FR55") (pin "1") (pinfunction "1_1") (pintype "passive"))
      (node (ref "IC3") (pin "AF6") (pinfunction "VDD14_LNA_RFE_AF6") (pintype "power_in"))
    )
    (net (code "32") (name "Net-(IC3F-VDD14_RBB)") (class "Default")
      (node (ref "C174") (pin "1") (pinfunction "1_1") (pintype "passive"))
      (node (ref "FR53") (pin "1") (pinfunction "1_1") (pintype "passive"))
      (node (ref "IC3") (pin "AD4") (pinfunction "VDD14_RBB_AD4") (pintype "power_in"))
    )
    (net (code "33") (name "Net-(IC3F-VDD14_TIA_RFE)") (class "Default")
      (node (ref "C173") (pin "1") (pinfunction "1_1") (pintype "passive"))
      (node (ref "FR54") (pin "1") (pinfunction "1_1") (pintype "passive"))
      (node (ref "IC3") (pin "AF2") (pinfunction "VDD14_TIA_RFE_AF2") (pintype "power_in"))
    )
    (net (code "34") (name "Net-(IC3F-VDD14_VCO_CGEN)") (class "Default")
      (node (ref "C171") (pin "1") (pinfunction "1_1") (pintype "passive"))
      (node (ref "FR56") (pin "1") (pinfunction "1_1") (pintype "passive"))
      (node (ref "IC3") (pin "C21") (pinfunction "VDD14_VCO_CGEN_C21") (pintype "power_in"))
    )
    (net (code "35") (name "Net-(IC3F-VDDO_DIV_SXT)") (class "Default")
      (node (ref "C170") (pin "1") (pinfunction "1_1") (pintype "passive"))
      (node (ref "FR51") (pin "1") (pinfunction "1_1") (pintype "passive"))
      (node (ref "IC3") (pin "K2") (pinfunction "VDDO_DIV_SXT_K2") (pintype "power_in"))
      (node (ref "IC3") (pin "L5") (pinfunction "VDD_DIV_SXT_L5") (pintype "power_in"))
    )
    (net (code "36") (name "Net-(IC3F-VDDO_TLOBUF_TRF)") (class "Default")
      (node (ref "C156") (pin "1") (pinfunction "1_1") (pintype "passive"))
      (node (ref "FR50") (pin "1") (pinfunction "1_1") (pintype "passive"))
      (node (ref "IC3") (pin "D6") (pinfunction "VDDO_TLOBUF_TRF_D6") (pintype "power_in"))
      (node (ref "IC3") (pin "F8") (pinfunction "VDD_TLOBUF_TRF_F8") (pintype "power_in"))
    )
    (net (code "37") (name "Net-(IC3F-VDD_AFE)") (class "Default")
      (node (ref "C160") (pin "1") (pinfunction "1_1") (pintype "passive"))
      (node (ref "FR46") (pin "1") (pinfunction "1_1") (pintype "passive"))
      (node (ref "IC3") (pin "AJ25") (pinfunction "VDD_AFE_AJ25") (pintype "power_in"))
    )
    (net (code "38") (name "Net-(IC3F-VDD_CP_CGEN)") (class "Default")
      (node (ref "C159") (pin "2") (pinfunction "2_2") (pintype "passive"))
      (node (ref "FR47") (pin "1") (pinfunction "1_1") (pintype "passive"))
      (node (ref "IC3") (pin "F20") (pinfunction "VDD_CP_CGEN_F20") (pintype "power_in"))
    )
    (net (code "39") (name "Net-(IC3F-VDD_CP_SXR)") (class "Default")
      (node (ref "C164") (pin "1") (pinfunction "1_1") (pintype "passive"))
      (node (ref "FR42") (pin "1") (pinfunction "1_1") (pintype "passive"))
      (node (ref "IC3") (pin "AL19") (pinfunction "VDD_CP_SXR_AL19") (pintype "power_in"))
    )
    (net (code "40") (name "Net-(IC3F-VDD_CP_SXT)") (class "Default")
      (node (ref "C167") (pin "1") (pinfunction "1_1") (pintype "passive"))
      (node (ref "FR38") (pin "1") (pinfunction "1_1") (pintype "passive"))
      (node (ref "IC3") (pin "J3") (pinfunction "VDD_CP_SXT_J3") (pintype "power_in"))
    )
    (net (code "41") (name "Net-(IC3F-VDD_DIV_CGEN)") (class "Default")
      (node (ref "C158") (pin "1") (pinfunction "1_1") (pintype "passive"))
      (node (ref "FR48") (pin "1") (pinfunction "1_1") (pintype "passive"))
      (node (ref "IC3") (pin "E19") (pinfunction "VDD_DIV_CGEN_E19") (pintype "power_in"))
    )
    (net (code "42") (name "Net-(IC3F-VDD_DIV_SXR)") (class "Default")
      (node (ref "C163") (pin "1") (pinfunction "1_1") (pintype "passive"))
      (node (ref "FR43") (pin "1") (pinfunction "1_1") (pintype "passive"))
      (node (ref "IC3") (pin "AM20") (pinfunction "VDD_DIV_SXR_AM20") (pintype "power_in"))
    )
    (net (code "43") (name "Net-(IC3F-VDD_MXLOBUF_RFE)") (class "Default")
      (node (ref "C175") (pin "1") (pinfunction "1_1") (pintype "passive"))
      (node (ref "FR52") (pin "1") (pinfunction "1_1") (pintype "passive"))
      (node (ref "IC3") (pin "AN17") (pinfunction "VDD_MXLOBUF_RFE_AN17") (pintype "power_in"))
    )
    (net (code "44") (name "Net-(IC3F-VDD_TBB)") (class "Default")
      (node (ref "C155") (pin "1") (pinfunction "1_1") (pintype "passive"))
      (node (ref "FR39") (pin "1") (pinfunction "1_1") (pintype "passive"))
      (node (ref "IC3") (pin "P4") (pinfunction "VDD_TBB_P4") (pintype "power_in"))
    )
    (net (code "45") (name "Net-(IC3F-VDD_TPAD_TRF)") (class "Default")
      (node (ref "C157") (pin "1") (pinfunction "1_1") (pintype "passive"))
      (node (ref "FR49") (pin "1") (pinfunction "1_1") (pintype "passive"))
      (node (ref "IC3") (pin "B16") (pinfunction "VDD_TPAD_TRF_B16") (pintype "power_in"))
    )
    (net (code "46") (name "VCC1P4_LMS2") (class "Default")
      (node (ref "FR51") (pin "2") (pinfunction "2_2") (pintype "passive"))
      (node (ref "FR52") (pin "2") (pinfunction "2_2") (pintype "passive"))
      (node (ref "FR53") (pin "2") (pinfunction "2_2") (pintype "passive"))
      (node (ref "FR54") (pin "2") (pinfunction "2_2") (pintype "passive"))
      (node (ref "FR55") (pin "2") (pinfunction "2_2") (pintype "passive"))
      (node (ref "FR56") (pin "2") (pinfunction "2_2") (pintype "passive"))
      (node (ref "R87") (pin "1") (pinfunction "1_1") (pintype "passive"))
    )
    (net (code "47") (name "VCC1P8_LMS2") (class "Default")
      (node (ref "FR57") (pin "2") (pinfunction "2_2") (pintype "passive"))
      (node (ref "FR58") (pin "1") (pinfunction "1_1") (pintype "passive"))
      (node (ref "FR59") (pin "1") (pinfunction "1_1") (pintype "passive"))
      (node (ref "FR60") (pin "2") (pinfunction "2_2") (pintype "passive"))
      (node (ref "FR61") (pin "2") (pinfunction "2_2") (pintype "passive"))
      (node (ref "FR62") (pin "2") (pinfunction "2_2") (pintype "passive"))
      (node (ref "FR63") (pin "2") (pinfunction "2_2") (pintype "passive"))
      (node (ref "FR64") (pin "2") (pinfunction "2_2") (pintype "passive"))
      (node (ref "R91") (pin "2") (pinfunction "2_2") (pintype "passive"))
      (node (ref "R97") (pin "2") (pinfunction "2_2") (pintype "passive"))
      (node (ref "R98") (pin "1") (pinfunction "1_1") (pintype "passive"))
    )
    (net (code "48") (name "VCC1P25_LMS2") (class "Default")
      (node (ref "FR34") (pin "2") (pinfunction "2_2") (pintype "passive"))
      (node (ref "FR35") (pin "2") (pinfunction "2_2") (pintype "passive"))
      (node (ref "FR36") (pin "2") (pinfunction "2_2") (pintype "passive"))
      (node (ref "FR37") (pin "2") (pinfunction "2_2") (pintype "passive"))
      (node (ref "FR38") (pin "2") (pinfunction "2_2") (pintype "passive"))
      (node (ref "FR39") (pin "2") (pinfunction "2_2") (pintype "passive"))
      (node (ref "FR40") (pin "2") (pinfunction "2_2") (pintype "passive"))
      (node (ref "FR41") (pin "2") (pinfunction "2_2") (pintype "passive"))
      (node (ref "FR42") (pin "2") (pinfunction "2_2") (pintype "passive"))
      (node (ref "FR43") (pin "2") (pinfunction "2_2") (pintype "passive"))
      (node (ref "FR44") (pin "2") (pinfunction "2_2") (pintype "passive"))
      (node (ref "FR45") (pin "2") (pinfunction "2_2") (pintype "passive"))
      (node (ref "FR46") (pin "2") (pinfunction "2_2") (pintype "passive"))
      (node (ref "FR47") (pin "2") (pinfunction "2_2") (pintype "passive"))
      (node (ref "FR48") (pin "2") (pinfunction "2_2") (pintype "passive"))
      (node (ref "FR49") (pin "2") (pinfunction "2_2") (pintype "passive"))
      (node (ref "FR50") (pin "2") (pinfunction "2_2") (pintype "passive"))
      (node (ref "R88") (pin "1") (pinfunction "1_1") (pintype "passive"))
    )
    (net (code "49") (name "VDIO_LMS") (class "Default")
      (node (ref "C177") (pin "2") (pinfunction "2_2") (pintype "passive"))
      (node (ref "R92") (pin "1") (pinfunction "1_1") (pintype "passive"))
      (node (ref "R93") (pin "1") (pinfunction "1_1") (pintype "passive"))
      (node (ref "R94") (pin "1") (pinfunction "1_1") (pintype "passive"))
      (node (ref "R95") (pin "1") (pinfunction "1_1") (pintype "passive"))
      (node (ref "R96") (pin "1") (pinfunction "1_1") (pintype "passive"))
    )
  )
)
